# Protoboard_MX2-7-6.net
KiCad netlist of a schematic drawn in EAGLE
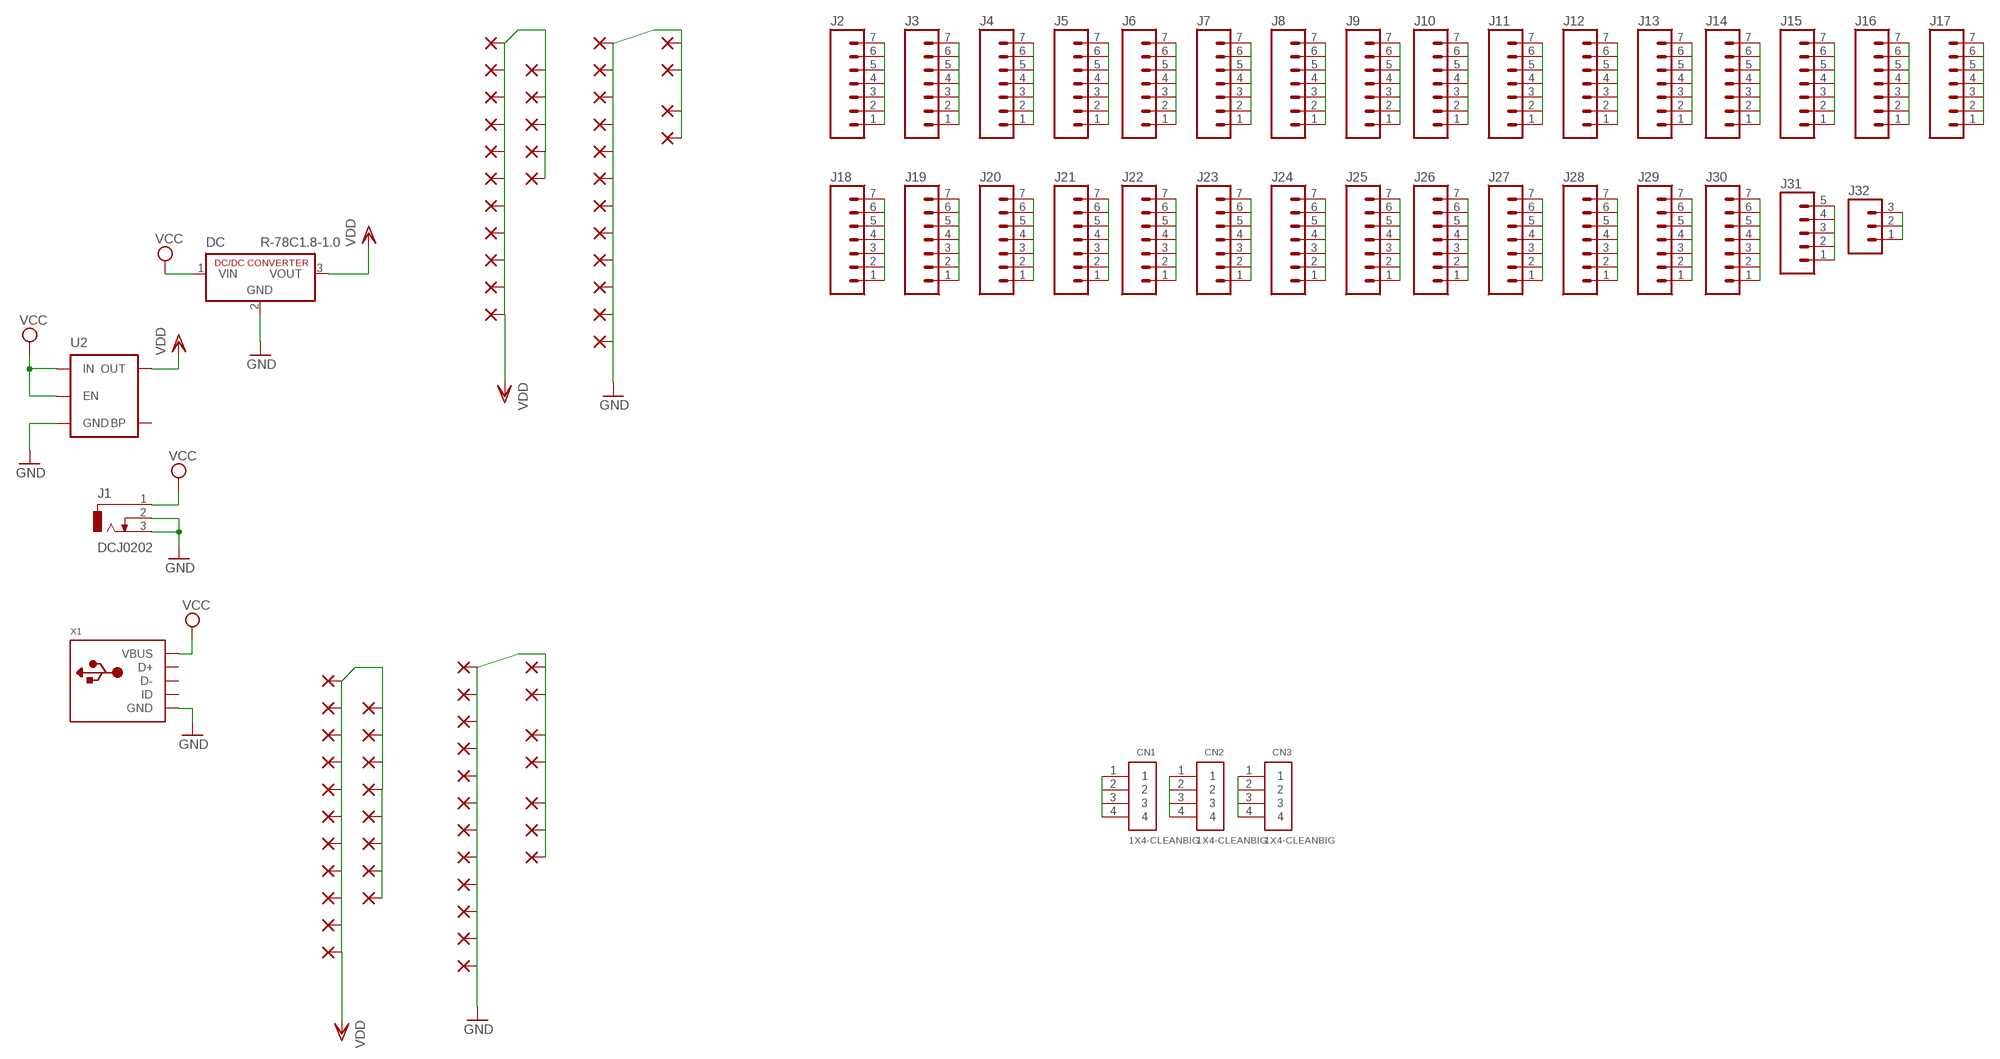
[diagram p0: schematic, sheet 1]

(export (version "E")
  (design (tool "Eeschema 10.0.6"))
  (components
    (comp (ref "CN1")
      (value "1X4-CLEANBIG")
      (footprint "eagle-import:1X04-CLEANBIG")
      (libsource (lib "eagle-import") (part "1X4-CLEANBIG"))
    )
    (comp (ref "CN2")
      (value "1X4-CLEANBIG")
      (footprint "eagle-import:1X04-CLEANBIG")
      (libsource (lib "eagle-import") (part "1X4-CLEANBIG"))
    )
    (comp (ref "CN3")
      (value "1X4-CLEANBIG")
      (footprint "eagle-import:1X04-CLEANBIG")
      (libsource (lib "eagle-import") (part "1X4-CLEANBIG"))
    )
    (comp (ref "DC")
      (value "R-78C1.8-1.0")
      (footprint "eagle-import:SIP3")
      (libsource (lib "eagle-import") (part "R-78C-1.01.8"))
    )
    (comp (ref "J1")
      (value "DCJ0202")
      (footprint "eagle-import:DCJ0202")
      (libsource (lib "eagle-import") (part "DCJ0202"))
    )
    (comp (ref "J2")
      (value "M07NO_SILK")
      (footprint "eagle-import:1X07_NO_SILK")
      (libsource (lib "eagle-import") (part "M07NO_SILK"))
    )
    (comp (ref "J3")
      (value "M07NO_SILK")
      (footprint "eagle-import:1X07_NO_SILK")
      (libsource (lib "eagle-import") (part "M07NO_SILK"))
    )
    (comp (ref "J4")
      (value "M07NO_SILK")
      (footprint "eagle-import:1X07_NO_SILK")
      (libsource (lib "eagle-import") (part "M07NO_SILK"))
    )
    (comp (ref "J5")
      (value "M07NO_SILK")
      (footprint "eagle-import:1X07_NO_SILK")
      (libsource (lib "eagle-import") (part "M07NO_SILK"))
    )
    (comp (ref "J6")
      (value "M07NO_SILK")
      (footprint "eagle-import:1X07_NO_SILK")
      (libsource (lib "eagle-import") (part "M07NO_SILK"))
    )
    (comp (ref "J7")
      (value "M07NO_SILK")
      (footprint "eagle-import:1X07_NO_SILK")
      (libsource (lib "eagle-import") (part "M07NO_SILK"))
    )
    (comp (ref "J8")
      (value "M07NO_SILK")
      (footprint "eagle-import:1X07_NO_SILK")
      (libsource (lib "eagle-import") (part "M07NO_SILK"))
    )
    (comp (ref "J9")
      (value "M07NO_SILK")
      (footprint "eagle-import:1X07_NO_SILK")
      (libsource (lib "eagle-import") (part "M07NO_SILK"))
    )
    (comp (ref "J10")
      (value "M07NO_SILK")
      (footprint "eagle-import:1X07_NO_SILK")
      (libsource (lib "eagle-import") (part "M07NO_SILK"))
    )
    (comp (ref "J11")
      (value "M07NO_SILK")
      (footprint "eagle-import:1X07_NO_SILK")
      (libsource (lib "eagle-import") (part "M07NO_SILK"))
    )
    (comp (ref "J12")
      (value "M07NO_SILK")
      (footprint "eagle-import:1X07_NO_SILK")
      (libsource (lib "eagle-import") (part "M07NO_SILK"))
    )
    (comp (ref "J13")
      (value "M07NO_SILK")
      (footprint "eagle-import:1X07_NO_SILK")
      (libsource (lib "eagle-import") (part "M07NO_SILK"))
    )
    (comp (ref "J14")
      (value "M07NO_SILK")
      (footprint "eagle-import:1X07_NO_SILK")
      (libsource (lib "eagle-import") (part "M07NO_SILK"))
    )
    (comp (ref "J15")
      (value "M07NO_SILK")
      (footprint "eagle-import:1X07_NO_SILK")
      (libsource (lib "eagle-import") (part "M07NO_SILK"))
    )
    (comp (ref "J16")
      (value "M07NO_SILK")
      (footprint "eagle-import:1X07_NO_SILK")
      (libsource (lib "eagle-import") (part "M07NO_SILK"))
    )
    (comp (ref "J17")
      (value "M07NO_SILK")
      (footprint "eagle-import:1X07_NO_SILK")
      (libsource (lib "eagle-import") (part "M07NO_SILK"))
    )
    (comp (ref "J18")
      (value "M07NO_SILK")
      (footprint "eagle-import:1X07_NO_SILK")
      (libsource (lib "eagle-import") (part "M07NO_SILK"))
    )
    (comp (ref "J19")
      (value "M07NO_SILK")
      (footprint "eagle-import:1X07_NO_SILK")
      (libsource (lib "eagle-import") (part "M07NO_SILK"))
    )
    (comp (ref "J20")
      (value "M07NO_SILK")
      (footprint "eagle-import:1X07_NO_SILK")
      (libsource (lib "eagle-import") (part "M07NO_SILK"))
    )
    (comp (ref "J21")
      (value "M07NO_SILK")
      (footprint "eagle-import:1X07_NO_SILK")
      (libsource (lib "eagle-import") (part "M07NO_SILK"))
    )
    (comp (ref "J22")
      (value "M07NO_SILK")
      (footprint "eagle-import:1X07_NO_SILK")
      (libsource (lib "eagle-import") (part "M07NO_SILK"))
    )
    (comp (ref "J23")
      (value "M07NO_SILK")
      (footprint "eagle-import:1X07_NO_SILK")
      (libsource (lib "eagle-import") (part "M07NO_SILK"))
    )
    (comp (ref "J24")
      (value "M07NO_SILK")
      (footprint "eagle-import:1X07_NO_SILK")
      (libsource (lib "eagle-import") (part "M07NO_SILK"))
    )
    (comp (ref "J25")
      (value "M07NO_SILK")
      (footprint "eagle-import:1X07_NO_SILK")
      (libsource (lib "eagle-import") (part "M07NO_SILK"))
    )
    (comp (ref "J26")
      (value "M07NO_SILK")
      (footprint "eagle-import:1X07_NO_SILK")
      (libsource (lib "eagle-import") (part "M07NO_SILK"))
    )
    (comp (ref "J27")
      (value "M07NO_SILK")
      (footprint "eagle-import:1X07_NO_SILK")
      (libsource (lib "eagle-import") (part "M07NO_SILK"))
    )
    (comp (ref "J28")
      (value "M07NO_SILK")
      (footprint "eagle-import:1X07_NO_SILK")
      (libsource (lib "eagle-import") (part "M07NO_SILK"))
    )
    (comp (ref "J29")
      (value "M07NO_SILK")
      (footprint "eagle-import:1X07_NO_SILK")
      (libsource (lib "eagle-import") (part "M07NO_SILK"))
    )
    (comp (ref "J30")
      (value "M07NO_SILK")
      (footprint "eagle-import:1X07_NO_SILK")
      (libsource (lib "eagle-import") (part "M07NO_SILK"))
    )
    (comp (ref "J31")
      (value "M05NO_SILK")
      (footprint "eagle-import:1X05_NO_SILK")
      (libsource (lib "eagle-import") (part "M05NO_SILK"))
    )
    (comp (ref "J32")
      (value "M031X03_NO_SILK")
      (footprint "eagle-import:1X03_NO_SILK")
      (libsource (lib "eagle-import") (part "M031X03_NO_SILK"))
    )
    (comp (ref "PAD4")
      (value "1,6/0,8")
      (footprint "eagle-import:1,6_0,8")
      (libsource (lib "eagle-import") (part "1,6/0,8"))
    )
    (comp (ref "PAD5")
      (value "1,6/0,8")
      (footprint "eagle-import:1,6_0,8")
      (libsource (lib "eagle-import") (part "1,6/0,8"))
    )
    (comp (ref "PAD6")
      (value "1,6/0,8")
      (footprint "eagle-import:1,6_0,8")
      (libsource (lib "eagle-import") (part "1,6/0,8"))
    )
    (comp (ref "PAD7")
      (value "1,6/0,8")
      (footprint "eagle-import:1,6_0,8")
      (libsource (lib "eagle-import") (part "1,6/0,8"))
    )
    (comp (ref "PAD8")
      (value "1,6/0,8")
      (footprint "eagle-import:1,6_0,8")
      (libsource (lib "eagle-import") (part "1,6/0,8"))
    )
    (comp (ref "PAD9")
      (value "1,6/0,8")
      (footprint "eagle-import:1,6_0,8")
      (libsource (lib "eagle-import") (part "1,6/0,8"))
    )
    (comp (ref "PAD10")
      (value "1,6/0,8")
      (footprint "eagle-import:1,6_0,8")
      (libsource (lib "eagle-import") (part "1,6/0,8"))
    )
    (comp (ref "PAD11")
      (value "1,6/0,8")
      (footprint "eagle-import:1,6_0,8")
      (libsource (lib "eagle-import") (part "1,6/0,8"))
    )
    (comp (ref "PAD12")
      (value "1,6/0,8")
      (footprint "eagle-import:1,6_0,8")
      (libsource (lib "eagle-import") (part "1,6/0,8"))
    )
    (comp (ref "PAD13")
      (value "1,6/0,8")
      (footprint "eagle-import:1,6_0,8")
      (libsource (lib "eagle-import") (part "1,6/0,8"))
    )
    (comp (ref "PAD14")
      (value "1,6/0,8")
      (footprint "eagle-import:1,6_0,8")
      (libsource (lib "eagle-import") (part "1,6/0,8"))
    )
    (comp (ref "PAD15")
      (value "1,6/0,8")
      (footprint "eagle-import:1,6_0,8")
      (libsource (lib "eagle-import") (part "1,6/0,8"))
    )
    (comp (ref "PAD16")
      (value "1,6/0,8")
      (footprint "eagle-import:1,6_0,8")
      (libsource (lib "eagle-import") (part "1,6/0,8"))
    )
    (comp (ref "PAD17")
      (value "1,6/0,8")
      (footprint "eagle-import:1,6_0,8")
      (libsource (lib "eagle-import") (part "1,6/0,8"))
    )
    (comp (ref "PAD18")
      (value "1,6/0,8")
      (footprint "eagle-import:1,6_0,8")
      (libsource (lib "eagle-import") (part "1,6/0,8"))
    )
    (comp (ref "PAD19")
      (value "1,6/0,8")
      (footprint "eagle-import:1,6_0,8")
      (libsource (lib "eagle-import") (part "1,6/0,8"))
    )
    (comp (ref "PAD20")
      (value "1,6/0,8")
      (footprint "eagle-import:1,6_0,8")
      (libsource (lib "eagle-import") (part "1,6/0,8"))
    )
    (comp (ref "PAD21")
      (value "1,6/0,8")
      (footprint "eagle-import:1,6_0,8")
      (libsource (lib "eagle-import") (part "1,6/0,8"))
    )
    (comp (ref "PAD22")
      (value "1,6/0,8")
      (footprint "eagle-import:1,6_0,8")
      (libsource (lib "eagle-import") (part "1,6/0,8"))
    )
    (comp (ref "PAD23")
      (value "1,6/0,8")
      (footprint "eagle-import:1,6_0,8")
      (libsource (lib "eagle-import") (part "1,6/0,8"))
    )
    (comp (ref "PAD24")
      (value "1,6/0,8")
      (footprint "eagle-import:1,6_0,8")
      (libsource (lib "eagle-import") (part "1,6/0,8"))
    )
    (comp (ref "PAD25")
      (value "1,6/0,8")
      (footprint "eagle-import:1,6_0,8")
      (libsource (lib "eagle-import") (part "1,6/0,8"))
    )
    (comp (ref "PAD26")
      (value "1,6/0,8")
      (footprint "eagle-import:1,6_0,8")
      (libsource (lib "eagle-import") (part "1,6/0,8"))
    )
    (comp (ref "PAD27")
      (value "1,6/0,8")
      (footprint "eagle-import:1,6_0,8")
      (libsource (lib "eagle-import") (part "1,6/0,8"))
    )
    (comp (ref "PAD28")
      (value "1,6/0,8")
      (footprint "eagle-import:1,6_0,8")
      (libsource (lib "eagle-import") (part "1,6/0,8"))
    )
    (comp (ref "PAD29")
      (value "1,6/0,8")
      (footprint "eagle-import:1,6_0,8")
      (libsource (lib "eagle-import") (part "1,6/0,8"))
    )
    (comp (ref "PAD30")
      (value "1,6/0,8")
      (footprint "eagle-import:1,6_0,8")
      (libsource (lib "eagle-import") (part "1,6/0,8"))
    )
    (comp (ref "PAD31")
      (value "1,6/0,8")
      (footprint "eagle-import:1,6_0,8")
      (libsource (lib "eagle-import") (part "1,6/0,8"))
    )
    (comp (ref "PAD32")
      (value "1,6/0,8")
      (footprint "eagle-import:1,6_0,8")
      (libsource (lib "eagle-import") (part "1,6/0,8"))
    )
    (comp (ref "PAD33")
      (value "1,6/0,8")
      (footprint "eagle-import:1,6_0,8")
      (libsource (lib "eagle-import") (part "1,6/0,8"))
    )
    (comp (ref "PAD36")
      (value "1,6/0,8")
      (footprint "eagle-import:1,6_0,8")
      (libsource (lib "eagle-import") (part "1,6/0,8"))
    )
    (comp (ref "PAD38")
      (value "1,6/0,8")
      (footprint "eagle-import:1,6_0,8")
      (libsource (lib "eagle-import") (part "1,6/0,8"))
    )
    (comp (ref "PAD421")
      (value "1,6/0,8")
      (footprint "eagle-import:1,6_0,8")
      (libsource (lib "eagle-import") (part "1,6/0,8"))
    )
    (comp (ref "PAD422")
      (value "1,6/0,8")
      (footprint "eagle-import:1,6_0,8")
      (libsource (lib "eagle-import") (part "1,6/0,8"))
    )
    (comp (ref "PAD423")
      (value "1,6/0,8")
      (footprint "eagle-import:1,6_0,8")
      (libsource (lib "eagle-import") (part "1,6/0,8"))
    )
    (comp (ref "PAD424")
      (value "1,6/0,8")
      (footprint "eagle-import:1,6_0,8")
      (libsource (lib "eagle-import") (part "1,6/0,8"))
    )
    (comp (ref "PAD425")
      (value "1,6/0,8")
      (footprint "eagle-import:1,6_0,8")
      (libsource (lib "eagle-import") (part "1,6/0,8"))
    )
    (comp (ref "PAD426")
      (value "1,6/0,8")
      (footprint "eagle-import:1,6_0,8")
      (libsource (lib "eagle-import") (part "1,6/0,8"))
    )
    (comp (ref "PAD427")
      (value "1,6/0,8")
      (footprint "eagle-import:1,6_0,8")
      (libsource (lib "eagle-import") (part "1,6/0,8"))
    )
    (comp (ref "PAD428")
      (value "1,6/0,8")
      (footprint "eagle-import:1,6_0,8")
      (libsource (lib "eagle-import") (part "1,6/0,8"))
    )
    (comp (ref "PAD429")
      (value "1,6/0,8")
      (footprint "eagle-import:1,6_0,8")
      (libsource (lib "eagle-import") (part "1,6/0,8"))
    )
    (comp (ref "PAD430")
      (value "1,6/0,8")
      (footprint "eagle-import:1,6_0,8")
      (libsource (lib "eagle-import") (part "1,6/0,8"))
    )
    (comp (ref "PAD431")
      (value "1,6/0,8")
      (footprint "eagle-import:1,6_0,8")
      (libsource (lib "eagle-import") (part "1,6/0,8"))
    )
    (comp (ref "PAD432")
      (value "1,6/0,8")
      (footprint "eagle-import:1,6_0,8")
      (libsource (lib "eagle-import") (part "1,6/0,8"))
    )
    (comp (ref "PAD433")
      (value "1,6/0,8")
      (footprint "eagle-import:1,6_0,8")
      (libsource (lib "eagle-import") (part "1,6/0,8"))
    )
    (comp (ref "PAD434")
      (value "1,6/0,8")
      (footprint "eagle-import:1,6_0,8")
      (libsource (lib "eagle-import") (part "1,6/0,8"))
    )
    (comp (ref "PAD435")
      (value "1,6/0,8")
      (footprint "eagle-import:1,6_0,8")
      (libsource (lib "eagle-import") (part "1,6/0,8"))
    )
    (comp (ref "PAD436")
      (value "1,6/0,8")
      (footprint "eagle-import:1,6_0,8")
      (libsource (lib "eagle-import") (part "1,6/0,8"))
    )
    (comp (ref "PAD439")
      (value "1,6/0,8")
      (footprint "eagle-import:1,6_0,8")
      (libsource (lib "eagle-import") (part "1,6/0,8"))
    )
    (comp (ref "PAD440")
      (value "1,6/0,8")
      (footprint "eagle-import:1,6_0,8")
      (libsource (lib "eagle-import") (part "1,6/0,8"))
    )
    (comp (ref "PAD441")
      (value "1,6/0,8")
      (footprint "eagle-import:1,6_0,8")
      (libsource (lib "eagle-import") (part "1,6/0,8"))
    )
    (comp (ref "PAD442")
      (value "1,6/0,8")
      (footprint "eagle-import:1,6_0,8")
      (libsource (lib "eagle-import") (part "1,6/0,8"))
    )
    (comp (ref "PAD443")
      (value "1,6/0,8")
      (footprint "eagle-import:1,6_0,8")
      (libsource (lib "eagle-import") (part "1,6/0,8"))
    )
    (comp (ref "PAD444")
      (value "1,6/0,8")
      (footprint "eagle-import:1,6_0,8")
      (libsource (lib "eagle-import") (part "1,6/0,8"))
    )
    (comp (ref "PAD445")
      (value "1,6/0,8")
      (footprint "eagle-import:1,6_0,8")
      (libsource (lib "eagle-import") (part "1,6/0,8"))
    )
    (comp (ref "PAD446")
      (value "1,6/0,8")
      (footprint "eagle-import:1,6_0,8")
      (libsource (lib "eagle-import") (part "1,6/0,8"))
    )
    (comp (ref "PAD447")
      (value "1,6/0,8")
      (footprint "eagle-import:1,6_0,8")
      (libsource (lib "eagle-import") (part "1,6/0,8"))
    )
    (comp (ref "PAD448")
      (value "1,6/0,8")
      (footprint "eagle-import:1,6_0,8")
      (libsource (lib "eagle-import") (part "1,6/0,8"))
    )
    (comp (ref "PAD449")
      (value "1,6/0,8")
      (footprint "eagle-import:1,6_0,8")
      (libsource (lib "eagle-import") (part "1,6/0,8"))
    )
    (comp (ref "PAD450")
      (value "1,6/0,8")
      (footprint "eagle-import:1,6_0,8")
      (libsource (lib "eagle-import") (part "1,6/0,8"))
    )
    (comp (ref "PAD451")
      (value "1,6/0,8")
      (footprint "eagle-import:1,6_0,8")
      (libsource (lib "eagle-import") (part "1,6/0,8"))
    )
    (comp (ref "PAD452")
      (value "1,6/0,8")
      (footprint "eagle-import:1,6_0,8")
      (libsource (lib "eagle-import") (part "1,6/0,8"))
    )
    (comp (ref "PAD453")
      (value "1,6/0,8")
      (footprint "eagle-import:1,6_0,8")
      (libsource (lib "eagle-import") (part "1,6/0,8"))
    )
    (comp (ref "PAD454")
      (value "1,6/0,8")
      (footprint "eagle-import:1,6_0,8")
      (libsource (lib "eagle-import") (part "1,6/0,8"))
    )
    (comp (ref "PAD455")
      (value "1,6/0,8")
      (footprint "eagle-import:1,6_0,8")
      (libsource (lib "eagle-import") (part "1,6/0,8"))
    )
    (comp (ref "PAD456")
      (value "1,6/0,8")
      (footprint "eagle-import:1,6_0,8")
      (libsource (lib "eagle-import") (part "1,6/0,8"))
    )
    (comp (ref "PAD459")
      (value "1,6/0,8")
      (footprint "eagle-import:1,6_0,8")
      (libsource (lib "eagle-import") (part "1,6/0,8"))
    )
    (comp (ref "PAD460")
      (value "1,6/0,8")
      (footprint "eagle-import:1,6_0,8")
      (libsource (lib "eagle-import") (part "1,6/0,8"))
    )
    (comp (ref "PAD461")
      (value "1,6/0,8")
      (footprint "eagle-import:1,6_0,8")
      (libsource (lib "eagle-import") (part "1,6/0,8"))
    )
    (comp (ref "PAD462")
      (value "1,6/0,8")
      (footprint "eagle-import:1,6_0,8")
      (libsource (lib "eagle-import") (part "1,6/0,8"))
    )
    (comp (ref "U2")
      (value "MIC52053.3V")
      (footprint "eagle-import:SOT23-5")
      (libsource (lib "eagle-import") (part "MIC52053.3V"))
    )
    (comp (ref "X1")
      (value "USBMICRO_20329")
      (footprint "eagle-import:4UCONN_20329")
      (libsource (lib "eagle-import") (part "USBMICRO_20329"))
    )
  )
  (nets
    (net (code "1") (name "GND") (class "Default")
      (node (ref "DC") (pin "2") (pinfunction "GND_2") (pintype "passive"))
      (node (ref "J1") (pin "2") (pinfunction "2_2") (pintype "passive"))
      (node (ref "J1") (pin "3") (pinfunction "3_3") (pintype "passive"))
      (node (ref "PAD17") (pin "1") (pinfunction "P_1") (pintype "passive"))
      (node (ref "PAD22") (pin "1") (pinfunction "P_1") (pintype "passive"))
      (node (ref "PAD23") (pin "1") (pinfunction "P_1") (pintype "passive"))
      (node (ref "PAD24") (pin "1") (pinfunction "P_1") (pintype "passive"))
      (node (ref "PAD25") (pin "1") (pinfunction "P_1") (pintype "passive"))
      (node (ref "PAD26") (pin "1") (pinfunction "P_1") (pintype "passive"))
      (node (ref "PAD27") (pin "1") (pinfunction "P_1") (pintype "passive"))
      (node (ref "PAD28") (pin "1") (pinfunction "P_1") (pintype "passive"))
      (node (ref "PAD29") (pin "1") (pinfunction "P_1") (pintype "passive"))
      (node (ref "PAD30") (pin "1") (pinfunction "P_1") (pintype "passive"))
      (node (ref "PAD31") (pin "1") (pinfunction "P_1") (pintype "passive"))
      (node (ref "PAD32") (pin "1") (pinfunction "P_1") (pintype "passive"))
      (node (ref "PAD33") (pin "1") (pinfunction "P_1") (pintype "passive"))
      (node (ref "PAD36") (pin "1") (pinfunction "P_1") (pintype "passive"))
      (node (ref "PAD38") (pin "1") (pinfunction "P_1") (pintype "passive"))
      (node (ref "PAD4") (pin "1") (pinfunction "P_1") (pintype "passive"))
      (node (ref "PAD421") (pin "1") (pinfunction "P_1") (pintype "passive"))
      (node (ref "PAD422") (pin "1") (pinfunction "P_1") (pintype "passive"))
      (node (ref "PAD423") (pin "1") (pinfunction "P_1") (pintype "passive"))
      (node (ref "PAD424") (pin "1") (pinfunction "P_1") (pintype "passive"))
      (node (ref "PAD425") (pin "1") (pinfunction "P_1") (pintype "passive"))
      (node (ref "PAD426") (pin "1") (pinfunction "P_1") (pintype "passive"))
      (node (ref "PAD427") (pin "1") (pinfunction "P_1") (pintype "passive"))
      (node (ref "PAD428") (pin "1") (pinfunction "P_1") (pintype "passive"))
      (node (ref "PAD429") (pin "1") (pinfunction "P_1") (pintype "passive"))
      (node (ref "PAD430") (pin "1") (pinfunction "P_1") (pintype "passive"))
      (node (ref "PAD431") (pin "1") (pinfunction "P_1") (pintype "passive"))
      (node (ref "PAD432") (pin "1") (pinfunction "P_1") (pintype "passive"))
      (node (ref "PAD433") (pin "1") (pinfunction "P_1") (pintype "passive"))
      (node (ref "PAD434") (pin "1") (pinfunction "P_1") (pintype "passive"))
      (node (ref "PAD435") (pin "1") (pinfunction "P_1") (pintype "passive"))
      (node (ref "PAD436") (pin "1") (pinfunction "P_1") (pintype "passive"))
      (node (ref "PAD439") (pin "1") (pinfunction "P_1") (pintype "passive"))
      (node (ref "PAD440") (pin "1") (pinfunction "P_1") (pintype "passive"))
      (node (ref "PAD441") (pin "1") (pinfunction "P_1") (pintype "passive"))
      (node (ref "U2") (pin "2") (pinfunction "GND_2") (pintype "input"))
      (node (ref "X1") (pin "BASE@1") (pinfunction "GND_BASE@1") (pintype "power_in"))
      (node (ref "X1") (pin "BASE@2") (pinfunction "GND_BASE@2") (pintype "power_in"))
      (node (ref "X1") (pin "GND") (pinfunction "GND_GND") (pintype "power_in"))
      (node (ref "X1") (pin "SPRT@1") (pinfunction "GND_SPRT@1") (pintype "power_in"))
      (node (ref "X1") (pin "SPRT@2") (pinfunction "GND_SPRT@2") (pintype "power_in"))
      (node (ref "X1") (pin "SPRT@3") (pinfunction "GND_SPRT@3") (pintype "power_in"))
      (node (ref "X1") (pin "SPRT@4") (pinfunction "GND_SPRT@4") (pintype "power_in"))
    )
    (net (code "2") (name "Net-(CN1-Pad1)") (class "Default")
      (node (ref "CN1") (pin "1") (pinfunction "1_1") (pintype "bidirectional"))
      (node (ref "CN1") (pin "2") (pinfunction "2_2") (pintype "bidirectional"))
      (node (ref "CN1") (pin "3") (pinfunction "3_3") (pintype "bidirectional"))
      (node (ref "CN1") (pin "4") (pinfunction "4_4") (pintype "bidirectional"))
    )
    (net (code "3") (name "Net-(CN2-Pad1)") (class "Default")
      (node (ref "CN2") (pin "1") (pinfunction "1_1") (pintype "bidirectional"))
      (node (ref "CN2") (pin "2") (pinfunction "2_2") (pintype "bidirectional"))
      (node (ref "CN2") (pin "3") (pinfunction "3_3") (pintype "bidirectional"))
      (node (ref "CN2") (pin "4") (pinfunction "4_4") (pintype "bidirectional"))
    )
    (net (code "4") (name "Net-(CN3-Pad1)") (class "Default")
      (node (ref "CN3") (pin "1") (pinfunction "1_1") (pintype "bidirectional"))
      (node (ref "CN3") (pin "2") (pinfunction "2_2") (pintype "bidirectional"))
      (node (ref "CN3") (pin "3") (pinfunction "3_3") (pintype "bidirectional"))
      (node (ref "CN3") (pin "4") (pinfunction "4_4") (pintype "bidirectional"))
    )
    (net (code "5") (name "Net-(J2-Pad1)") (class "Default")
      (node (ref "J2") (pin "1") (pinfunction "1_1") (pintype "passive"))
      (node (ref "J2") (pin "2") (pinfunction "2_2") (pintype "passive"))
      (node (ref "J2") (pin "3") (pinfunction "3_3") (pintype "passive"))
      (node (ref "J2") (pin "4") (pinfunction "4_4") (pintype "passive"))
      (node (ref "J2") (pin "5") (pinfunction "5_5") (pintype "passive"))
      (node (ref "J2") (pin "6") (pinfunction "6_6") (pintype "passive"))
      (node (ref "J2") (pin "7") (pinfunction "7_7") (pintype "passive"))
    )
    (net (code "6") (name "Net-(J3-Pad1)") (class "Default")
      (node (ref "J3") (pin "1") (pinfunction "1_1") (pintype "passive"))
      (node (ref "J3") (pin "2") (pinfunction "2_2") (pintype "passive"))
      (node (ref "J3") (pin "3") (pinfunction "3_3") (pintype "passive"))
      (node (ref "J3") (pin "4") (pinfunction "4_4") (pintype "passive"))
      (node (ref "J3") (pin "5") (pinfunction "5_5") (pintype "passive"))
      (node (ref "J3") (pin "6") (pinfunction "6_6") (pintype "passive"))
      (node (ref "J3") (pin "7") (pinfunction "7_7") (pintype "passive"))
    )
    (net (code "7") (name "Net-(J4-Pad1)") (class "Default")
      (node (ref "J4") (pin "1") (pinfunction "1_1") (pintype "passive"))
      (node (ref "J4") (pin "2") (pinfunction "2_2") (pintype "passive"))
      (node (ref "J4") (pin "3") (pinfunction "3_3") (pintype "passive"))
      (node (ref "J4") (pin "4") (pinfunction "4_4") (pintype "passive"))
      (node (ref "J4") (pin "5") (pinfunction "5_5") (pintype "passive"))
      (node (ref "J4") (pin "6") (pinfunction "6_6") (pintype "passive"))
      (node (ref "J4") (pin "7") (pinfunction "7_7") (pintype "passive"))
    )
    (net (code "8") (name "Net-(J5-Pad1)") (class "Default")
      (node (ref "J5") (pin "1") (pinfunction "1_1") (pintype "passive"))
      (node (ref "J5") (pin "2") (pinfunction "2_2") (pintype "passive"))
      (node (ref "J5") (pin "3") (pinfunction "3_3") (pintype "passive"))
      (node (ref "J5") (pin "4") (pinfunction "4_4") (pintype "passive"))
      (node (ref "J5") (pin "5") (pinfunction "5_5") (pintype "passive"))
      (node (ref "J5") (pin "6") (pinfunction "6_6") (pintype "passive"))
      (node (ref "J5") (pin "7") (pinfunction "7_7") (pintype "passive"))
    )
    (net (code "9") (name "Net-(J6-Pad1)") (class "Default")
      (node (ref "J6") (pin "1") (pinfunction "1_1") (pintype "passive"))
      (node (ref "J6") (pin "2") (pinfunction "2_2") (pintype "passive"))
      (node (ref "J6") (pin "3") (pinfunction "3_3") (pintype "passive"))
      (node (ref "J6") (pin "4") (pinfunction "4_4") (pintype "passive"))
      (node (ref "J6") (pin "5") (pinfunction "5_5") (pintype "passive"))
      (node (ref "J6") (pin "6") (pinfunction "6_6") (pintype "passive"))
      (node (ref "J6") (pin "7") (pinfunction "7_7") (pintype "passive"))
    )
    (net (code "10") (name "Net-(J7-Pad1)") (class "Default")
      (node (ref "J7") (pin "1") (pinfunction "1_1") (pintype "passive"))
      (node (ref "J7") (pin "2") (pinfunction "2_2") (pintype "passive"))
      (node (ref "J7") (pin "3") (pinfunction "3_3") (pintype "passive"))
      (node (ref "J7") (pin "4") (pinfunction "4_4") (pintype "passive"))
      (node (ref "J7") (pin "5") (pinfunction "5_5") (pintype "passive"))
      (node (ref "J7") (pin "6") (pinfunction "6_6") (pintype "passive"))
      (node (ref "J7") (pin "7") (pinfunction "7_7") (pintype "passive"))
    )
    (net (code "11") (name "Net-(J8-Pad1)") (class "Default")
      (node (ref "J8") (pin "1") (pinfunction "1_1") (pintype "passive"))
      (node (ref "J8") (pin "2") (pinfunction "2_2") (pintype "passive"))
      (node (ref "J8") (pin "3") (pinfunction "3_3") (pintype "passive"))
      (node (ref "J8") (pin "4") (pinfunction "4_4") (pintype "passive"))
      (node (ref "J8") (pin "5") (pinfunction "5_5") (pintype "passive"))
      (node (ref "J8") (pin "6") (pinfunction "6_6") (pintype "passive"))
      (node (ref "J8") (pin "7") (pinfunction "7_7") (pintype "passive"))
    )
    (net (code "12") (name "Net-(J9-Pad1)") (class "Default")
      (node (ref "J9") (pin "1") (pinfunction "1_1") (pintype "passive"))
      (node (ref "J9") (pin "2") (pinfunction "2_2") (pintype "passive"))
      (node (ref "J9") (pin "3") (pinfunction "3_3") (pintype "passive"))
      (node (ref "J9") (pin "4") (pinfunction "4_4") (pintype "passive"))
      (node (ref "J9") (pin "5") (pinfunction "5_5") (pintype "passive"))
      (node (ref "J9") (pin "6") (pinfunction "6_6") (pintype "passive"))
      (node (ref "J9") (pin "7") (pinfunction "7_7") (pintype "passive"))
    )
    (net (code "13") (name "Net-(J10-Pad1)") (class "Default")
      (node (ref "J10") (pin "1") (pinfunction "1_1") (pintype "passive"))
      (node (ref "J10") (pin "2") (pinfunction "2_2") (pintype "passive"))
      (node (ref "J10") (pin "3") (pinfunction "3_3") (pintype "passive"))
      (node (ref "J10") (pin "4") (pinfunction "4_4") (pintype "passive"))
      (node (ref "J10") (pin "5") (pinfunction "5_5") (pintype "passive"))
      (node (ref "J10") (pin "6") (pinfunction "6_6") (pintype "passive"))
      (node (ref "J10") (pin "7") (pinfunction "7_7") (pintype "passive"))
    )
    (net (code "14") (name "Net-(J11-Pad1)") (class "Default")
      (node (ref "J11") (pin "1") (pinfunction "1_1") (pintype "passive"))
      (node (ref "J11") (pin "2") (pinfunction "2_2") (pintype "passive"))
      (node (ref "J11") (pin "3") (pinfunction "3_3") (pintype "passive"))
      (node (ref "J11") (pin "4") (pinfunction "4_4") (pintype "passive"))
      (node (ref "J11") (pin "5") (pinfunction "5_5") (pintype "passive"))
      (node (ref "J11") (pin "6") (pinfunction "6_6") (pintype "passive"))
      (node (ref "J11") (pin "7") (pinfunction "7_7") (pintype "passive"))
    )
    (net (code "15") (name "Net-(J12-Pad1)") (class "Default")
      (node (ref "J12") (pin "1") (pinfunction "1_1") (pintype "passive"))
      (node (ref "J12") (pin "2") (pinfunction "2_2") (pintype "passive"))
      (node (ref "J12") (pin "3") (pinfunction "3_3") (pintype "passive"))
      (node (ref "J12") (pin "4") (pinfunction "4_4") (pintype "passive"))
      (node (ref "J12") (pin "5") (pinfunction "5_5") (pintype "passive"))
      (node (ref "J12") (pin "6") (pinfunction "6_6") (pintype "passive"))
      (node (ref "J12") (pin "7") (pinfunction "7_7") (pintype "passive"))
    )
    (net (code "16") (name "Net-(J13-Pad1)") (class "Default")
      (node (ref "J13") (pin "1") (pinfunction "1_1") (pintype "passive"))
      (node (ref "J13") (pin "2") (pinfunction "2_2") (pintype "passive"))
      (node (ref "J13") (pin "3") (pinfunction "3_3") (pintype "passive"))
      (node (ref "J13") (pin "4") (pinfunction "4_4") (pintype "passive"))
      (node (ref "J13") (pin "5") (pinfunction "5_5") (pintype "passive"))
      (node (ref "J13") (pin "6") (pinfunction "6_6") (pintype "passive"))
      (node (ref "J13") (pin "7") (pinfunction "7_7") (pintype "passive"))
    )
    (net (code "17") (name "Net-(J14-Pad1)") (class "Default")
      (node (ref "J14") (pin "1") (pinfunction "1_1") (pintype "passive"))
      (node (ref "J14") (pin "2") (pinfunction "2_2") (pintype "passive"))
      (node (ref "J14") (pin "3") (pinfunction "3_3") (pintype "passive"))
      (node (ref "J14") (pin "4") (pinfunction "4_4") (pintype "passive"))
      (node (ref "J14") (pin "5") (pinfunction "5_5") (pintype "passive"))
      (node (ref "J14") (pin "6") (pinfunction "6_6") (pintype "passive"))
      (node (ref "J14") (pin "7") (pinfunction "7_7") (pintype "passive"))
    )
    (net (code "18") (name "Net-(J15-Pad1)") (class "Default")
      (node (ref "J15") (pin "1") (pinfunction "1_1") (pintype "passive"))
      (node (ref "J15") (pin "2") (pinfunction "2_2") (pintype "passive"))
      (node (ref "J15") (pin "3") (pinfunction "3_3") (pintype "passive"))
      (node (ref "J15") (pin "4") (pinfunction "4_4") (pintype "passive"))
      (node (ref "J15") (pin "5") (pinfunction "5_5") (pintype "passive"))
      (node (ref "J15") (pin "6") (pinfunction "6_6") (pintype "passive"))
      (node (ref "J15") (pin "7") (pinfunction "7_7") (pintype "passive"))
    )
    (net (code "19") (name "Net-(J16-Pad1)") (class "Default")
      (node (ref "J16") (pin "1") (pinfunction "1_1") (pintype "passive"))
      (node (ref "J16") (pin "2") (pinfunction "2_2") (pintype "passive"))
      (node (ref "J16") (pin "3") (pinfunction "3_3") (pintype "passive"))
      (node (ref "J16") (pin "4") (pinfunction "4_4") (pintype "passive"))
      (node (ref "J16") (pin "5") (pinfunction "5_5") (pintype "passive"))
      (node (ref "J16") (pin "6") (pinfunction "6_6") (pintype "passive"))
      (node (ref "J16") (pin "7") (pinfunction "7_7") (pintype "passive"))
    )
    (net (code "20") (name "Net-(J17-Pad1)") (class "Default")
      (node (ref "J17") (pin "1") (pinfunction "1_1") (pintype "passive"))
      (node (ref "J17") (pin "2") (pinfunction "2_2") (pintype "passive"))
      (node (ref "J17") (pin "3") (pinfunction "3_3") (pintype "passive"))
      (node (ref "J17") (pin "4") (pinfunction "4_4") (pintype "passive"))
      (node (ref "J17") (pin "5") (pinfunction "5_5") (pintype "passive"))
      (node (ref "J17") (pin "6") (pinfunction "6_6") (pintype "passive"))
      (node (ref "J17") (pin "7") (pinfunction "7_7") (pintype "passive"))
    )
    (net (code "21") (name "Net-(J18-Pad1)") (class "Default")
      (node (ref "J18") (pin "1") (pinfunction "1_1") (pintype "passive"))
      (node (ref "J18") (pin "2") (pinfunction "2_2") (pintype "passive"))
      (node (ref "J18") (pin "3") (pinfunction "3_3") (pintype "passive"))
      (node (ref "J18") (pin "4") (pinfunction "4_4") (pintype "passive"))
      (node (ref "J18") (pin "5") (pinfunction "5_5") (pintype "passive"))
      (node (ref "J18") (pin "6") (pinfunction "6_6") (pintype "passive"))
      (node (ref "J18") (pin "7") (pinfunction "7_7") (pintype "passive"))
    )
    (net (code "22") (name "Net-(J19-Pad1)") (class "Default")
      (node (ref "J19") (pin "1") (pinfunction "1_1") (pintype "passive"))
      (node (ref "J19") (pin "2") (pinfunction "2_2") (pintype "passive"))
      (node (ref "J19") (pin "3") (pinfunction "3_3") (pintype "passive"))
      (node (ref "J19") (pin "4") (pinfunction "4_4") (pintype "passive"))
      (node (ref "J19") (pin "5") (pinfunction "5_5") (pintype "passive"))
      (node (ref "J19") (pin "6") (pinfunction "6_6") (pintype "passive"))
      (node (ref "J19") (pin "7") (pinfunction "7_7") (pintype "passive"))
    )
    (net (code "23") (name "Net-(J20-Pad1)") (class "Default")
      (node (ref "J20") (pin "1") (pinfunction "1_1") (pintype "passive"))
      (node (ref "J20") (pin "2") (pinfunction "2_2") (pintype "passive"))
      (node (ref "J20") (pin "3") (pinfunction "3_3") (pintype "passive"))
      (node (ref "J20") (pin "4") (pinfunction "4_4") (pintype "passive"))
      (node (ref "J20") (pin "5") (pinfunction "5_5") (pintype "passive"))
      (node (ref "J20") (pin "6") (pinfunction "6_6") (pintype "passive"))
      (node (ref "J20") (pin "7") (pinfunction "7_7") (pintype "passive"))
    )
    (net (code "24") (name "Net-(J21-Pad1)") (class "Default")
      (node (ref "J21") (pin "1") (pinfunction "1_1") (pintype "passive"))
      (node (ref "J21") (pin "2") (pinfunction "2_2") (pintype "passive"))
      (node (ref "J21") (pin "3") (pinfunction "3_3") (pintype "passive"))
      (node (ref "J21") (pin "4") (pinfunction "4_4") (pintype "passive"))
      (node (ref "J21") (pin "5") (pinfunction "5_5") (pintype "passive"))
      (node (ref "J21") (pin "6") (pinfunction "6_6") (pintype "passive"))
      (node (ref "J21") (pin "7") (pinfunction "7_7") (pintype "passive"))
    )
    (net (code "25") (name "Net-(J22-Pad1)") (class "Default")
      (node (ref "J22") (pin "1") (pinfunction "1_1") (pintype "passive"))
      (node (ref "J22") (pin "2") (pinfunction "2_2") (pintype "passive"))
      (node (ref "J22") (pin "3") (pinfunction "3_3") (pintype "passive"))
      (node (ref "J22") (pin "4") (pinfunction "4_4") (pintype "passive"))
      (node (ref "J22") (pin "5") (pinfunction "5_5") (pintype "passive"))
      (node (ref "J22") (pin "6") (pinfunction "6_6") (pintype "passive"))
      (node (ref "J22") (pin "7") (pinfunction "7_7") (pintype "passive"))
    )
    (net (code "26") (name "Net-(J23-Pad1)") (class "Default")
      (node (ref "J23") (pin "1") (pinfunction "1_1") (pintype "passive"))
      (node (ref "J23") (pin "2") (pinfunction "2_2") (pintype "passive"))
      (node (ref "J23") (pin "3") (pinfunction "3_3") (pintype "passive"))
      (node (ref "J23") (pin "4") (pinfunction "4_4") (pintype "passive"))
      (node (ref "J23") (pin "5") (pinfunction "5_5") (pintype "passive"))
      (node (ref "J23") (pin "6") (pinfunction "6_6") (pintype "passive"))
      (node (ref "J23") (pin "7") (pinfunction "7_7") (pintype "passive"))
    )
    (net (code "27") (name "Net-(J24-Pad1)") (class "Default")
      (node (ref "J24") (pin "1") (pinfunction "1_1") (pintype "passive"))
      (node (ref "J24") (pin "2") (pinfunction "2_2") (pintype "passive"))
      (node (ref "J24") (pin "3") (pinfunction "3_3") (pintype "passive"))
      (node (ref "J24") (pin "4") (pinfunction "4_4") (pintype "passive"))
      (node (ref "J24") (pin "5") (pinfunction "5_5") (pintype "passive"))
      (node (ref "J24") (pin "6") (pinfunction "6_6") (pintype "passive"))
      (node (ref "J24") (pin "7") (pinfunction "7_7") (pintype "passive"))
    )
    (net (code "28") (name "Net-(J25-Pad1)") (class "Default")
      (node (ref "J25") (pin "1") (pinfunction "1_1") (pintype "passive"))
      (node (ref "J25") (pin "2") (pinfunction "2_2") (pintype "passive"))
      (node (ref "J25") (pin "3") (pinfunction "3_3") (pintype "passive"))
      (node (ref "J25") (pin "4") (pinfunction "4_4") (pintype "passive"))
      (node (ref "J25") (pin "5") (pinfunction "5_5") (pintype "passive"))
      (node (ref "J25") (pin "6") (pinfunction "6_6") (pintype "passive"))
      (node (ref "J25") (pin "7") (pinfunction "7_7") (pintype "passive"))
    )
    (net (code "29") (name "Net-(J26-Pad1)") (class "Default")
      (node (ref "J26") (pin "1") (pinfunction "1_1") (pintype "passive"))
      (node (ref "J26") (pin "2") (pinfunction "2_2") (pintype "passive"))
      (node (ref "J26") (pin "3") (pinfunction "3_3") (pintype "passive"))
      (node (ref "J26") (pin "4") (pinfunction "4_4") (pintype "passive"))
      (node (ref "J26") (pin "5") (pinfunction "5_5") (pintype "passive"))
      (node (ref "J26") (pin "6") (pinfunction "6_6") (pintype "passive"))
      (node (ref "J26") (pin "7") (pinfunction "7_7") (pintype "passive"))
    )
    (net (code "30") (name "Net-(J27-Pad1)") (class "Default")
      (node (ref "J27") (pin "1") (pinfunction "1_1") (pintype "passive"))
      (node (ref "J27") (pin "2") (pinfunction "2_2") (pintype "passive"))
      (node (ref "J27") (pin "3") (pinfunction "3_3") (pintype "passive"))
      (node (ref "J27") (pin "4") (pinfunction "4_4") (pintype "passive"))
      (node (ref "J27") (pin "5") (pinfunction "5_5") (pintype "passive"))
      (node (ref "J27") (pin "6") (pinfunction "6_6") (pintype "passive"))
      (node (ref "J27") (pin "7") (pinfunction "7_7") (pintype "passive"))
    )
    (net (code "31") (name "Net-(J28-Pad1)") (class "Default")
      (node (ref "J28") (pin "1") (pinfunction "1_1") (pintype "passive"))
      (node (ref "J28") (pin "2") (pinfunction "2_2") (pintype "passive"))
      (node (ref "J28") (pin "3") (pinfunction "3_3") (pintype "passive"))
      (node (ref "J28") (pin "4") (pinfunction "4_4") (pintype "passive"))
      (node (ref "J28") (pin "5") (pinfunction "5_5") (pintype "passive"))
      (node (ref "J28") (pin "6") (pinfunction "6_6") (pintype "passive"))
      (node (ref "J28") (pin "7") (pinfunction "7_7") (pintype "passive"))
    )
    (net (code "32") (name "Net-(J29-Pad1)") (class "Default")
      (node (ref "J29") (pin "1") (pinfunction "1_1") (pintype "passive"))
      (node (ref "J29") (pin "2") (pinfunction "2_2") (pintype "passive"))
      (node (ref "J29") (pin "3") (pinfunction "3_3") (pintype "passive"))
      (node (ref "J29") (pin "4") (pinfunction "4_4") (pintype "passive"))
      (node (ref "J29") (pin "5") (pinfunction "5_5") (pintype "passive"))
      (node (ref "J29") (pin "6") (pinfunction "6_6") (pintype "passive"))
      (node (ref "J29") (pin "7") (pinfunction "7_7") (pintype "passive"))
    )
    (net (code "33") (name "Net-(J30-Pad1)") (class "Default")
      (node (ref "J30") (pin "1") (pinfunction "1_1") (pintype "passive"))
      (node (ref "J30") (pin "2") (pinfunction "2_2") (pintype "passive"))
      (node (ref "J30") (pin "3") (pinfunction "3_3") (pintype "passive"))
      (node (ref "J30") (pin "4") (pinfunction "4_4") (pintype "passive"))
      (node (ref "J30") (pin "5") (pinfunction "5_5") (pintype "passive"))
      (node (ref "J30") (pin "6") (pinfunction "6_6") (pintype "passive"))
      (node (ref "J30") (pin "7") (pinfunction "7_7") (pintype "passive"))
    )
    (net (code "34") (name "Net-(J31-Pad1)") (class "Default")
      (node (ref "J31") (pin "1") (pinfunction "1_1") (pintype "passive"))
      (node (ref "J31") (pin "2") (pinfunction "2_2") (pintype "passive"))
      (node (ref "J31") (pin "3") (pinfunction "3_3") (pintype "passive"))
      (node (ref "J31") (pin "4") (pinfunction "4_4") (pintype "passive"))
      (node (ref "J31") (pin "5") (pinfunction "5_5") (pintype "passive"))
    )
    (net (code "35") (name "Net-(J32-Pad1)") (class "Default")
      (node (ref "J32") (pin "1") (pinfunction "1_1") (pintype "passive"))
      (node (ref "J32") (pin "2") (pinfunction "2_2") (pintype "passive"))
      (node (ref "J32") (pin "3") (pinfunction "3_3") (pintype "passive"))
    )
    (net (code "36") (name "VCC") (class "Default")
      (node (ref "DC") (pin "1") (pinfunction "VIN_1") (pintype "passive"))
      (node (ref "J1") (pin "1") (pinfunction "1_1") (pintype "passive"))
      (node (ref "U2") (pin "1") (pinfunction "IN_1") (pintype "input"))
      (node (ref "U2") (pin "3") (pinfunction "EN_3") (pintype "input"))
      (node (ref "X1") (pin "VBUS") (pinfunction "VBUS_VBUS") (pintype "power_in"))
    )
    (net (code "37") (name "VDD") (class "Default")
      (node (ref "DC") (pin "3") (pinfunction "VOUT_3") (pintype "passive"))
      (node (ref "PAD10") (pin "1") (pinfunction "P_1") (pintype "passive"))
      (node (ref "PAD11") (pin "1") (pinfunction "P_1") (pintype "passive"))
      (node (ref "PAD12") (pin "1") (pinfunction "P_1") (pintype "passive"))
      (node (ref "PAD13") (pin "1") (pinfunction "P_1") (pintype "passive"))
      (node (ref "PAD14") (pin "1") (pinfunction "P_1") (pintype "passive"))
      (node (ref "PAD15") (pin "1") (pinfunction "P_1") (pintype "passive"))
      (node (ref "PAD16") (pin "1") (pinfunction "P_1") (pintype "passive"))
      (node (ref "PAD18") (pin "1") (pinfunction "P_1") (pintype "passive"))
      (node (ref "PAD19") (pin "1") (pinfunction "P_1") (pintype "passive"))
      (node (ref "PAD20") (pin "1") (pinfunction "P_1") (pintype "passive"))
      (node (ref "PAD21") (pin "1") (pinfunction "P_1") (pintype "passive"))
      (node (ref "PAD442") (pin "1") (pinfunction "P_1") (pintype "passive"))
      (node (ref "PAD443") (pin "1") (pinfunction "P_1") (pintype "passive"))
      (node (ref "PAD444") (pin "1") (pinfunction "P_1") (pintype "passive"))
      (node (ref "PAD445") (pin "1") (pinfunction "P_1") (pintype "passive"))
      (node (ref "PAD446") (pin "1") (pinfunction "P_1") (pintype "passive"))
      (node (ref "PAD447") (pin "1") (pinfunction "P_1") (pintype "passive"))
      (node (ref "PAD448") (pin "1") (pinfunction "P_1") (pintype "passive"))
      (node (ref "PAD449") (pin "1") (pinfunction "P_1") (pintype "passive"))
      (node (ref "PAD450") (pin "1") (pinfunction "P_1") (pintype "passive"))
      (node (ref "PAD451") (pin "1") (pinfunction "P_1") (pintype "passive"))
      (node (ref "PAD452") (pin "1") (pinfunction "P_1") (pintype "passive"))
      (node (ref "PAD453") (pin "1") (pinfunction "P_1") (pintype "passive"))
      (node (ref "PAD454") (pin "1") (pinfunction "P_1") (pintype "passive"))
      (node (ref "PAD455") (pin "1") (pinfunction "P_1") (pintype "passive"))
      (node (ref "PAD456") (pin "1") (pinfunction "P_1") (pintype "passive"))
      (node (ref "PAD459") (pin "1") (pinfunction "P_1") (pintype "passive"))
      (node (ref "PAD460") (pin "1") (pinfunction "P_1") (pintype "passive"))
      (node (ref "PAD461") (pin "1") (pinfunction "P_1") (pintype "passive"))
      (node (ref "PAD462") (pin "1") (pinfunction "P_1") (pintype "passive"))
      (node (ref "PAD5") (pin "1") (pinfunction "P_1") (pintype "passive"))
      (node (ref "PAD6") (pin "1") (pinfunction "P_1") (pintype "passive"))
      (node (ref "PAD7") (pin "1") (pinfunction "P_1") (pintype "passive"))
      (node (ref "PAD8") (pin "1") (pinfunction "P_1") (pintype "passive"))
      (node (ref "PAD9") (pin "1") (pinfunction "P_1") (pintype "passive"))
      (node (ref "U2") (pin "5") (pinfunction "OUT_5") (pintype "passive"))
    )
    (net (code "38") (name "unconnected-(U2-BP-Pad4)") (class "Default")
      (node (ref "U2") (pin "4") (pinfunction "BP_4") (pintype "input"))
    )
    (net (code "39") (name "unconnected-(X1-PadD+)") (class "Default")
      (node (ref "X1") (pin "D+") (pinfunction "D+_D+") (pintype "bidirectional"))
    )
    (net (code "40") (name "unconnected-(X1-PadD-)") (class "Default")
      (node (ref "X1") (pin "D-") (pinfunction "D-_D-") (pintype "bidirectional"))
    )
    (net (code "41") (name "unconnected-(X1-PadID)") (class "Default")
      (node (ref "X1") (pin "ID") (pinfunction "ID_ID") (pintype "bidirectional"))
    )
  )
)
